# emote-esp8266.net
KiCad netlist of a schematic drawn in EAGLE
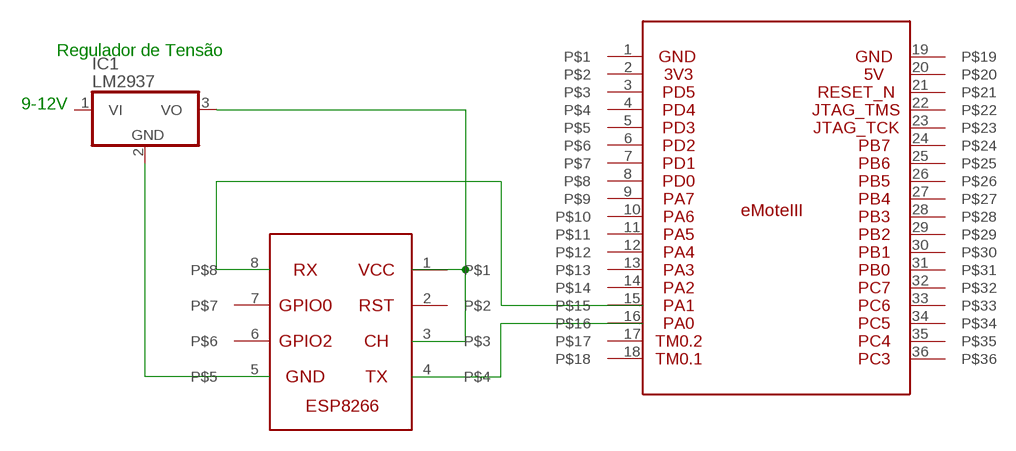
[diagram p0: schematic, sheet 1]

(export (version "E")
  (design (tool "Eeschema 10.0.6"))
  (components
    (comp (ref "IC1")
      (value "LM2937")
      (footprint "eagle-import:TO263-3")
      (libsource (lib "eagle-import") (part "LM2937"))
    )
    (comp (ref "U$1")
      (value "EMOTE3")
      (footprint "eagle-import:2X18")
      (libsource (lib "eagle-import") (part "EMOTE3"))
    )
    (comp (ref "U$2")
      (value "ESP8266")
      (footprint "eagle-import:332-08")
      (libsource (lib "eagle-import") (part "ESP8266"))
    )
  )
  (nets
    (net (code "1") (name "Net-(IC1-GND)") (class "Default")
      (node (ref "IC1") (pin "2") (pinfunction "GND_2") (pintype "passive"))
      (node (ref "U$2") (pin "5") (pinfunction "P$5_5") (pintype "bidirectional"))
    )
    (net (code "2") (name "Net-(IC1-VO)") (class "Default")
      (node (ref "IC1") (pin "3") (pinfunction "VO_3") (pintype "passive"))
      (node (ref "U$2") (pin "1") (pinfunction "P$1_1") (pintype "bidirectional"))
      (node (ref "U$2") (pin "3") (pinfunction "P$3_3") (pintype "bidirectional"))
    )
    (net (code "3") (name "Net-(U$1-P$15)") (class "Default")
      (node (ref "U$1") (pin "15") (pinfunction "P$15_15") (pintype "bidirectional"))
      (node (ref "U$2") (pin "8") (pinfunction "P$8_8") (pintype "bidirectional"))
    )
    (net (code "4") (name "Net-(U$1-P$16)") (class "Default")
      (node (ref "U$1") (pin "16") (pinfunction "P$16_16") (pintype "bidirectional"))
      (node (ref "U$2") (pin "4") (pinfunction "P$4_4") (pintype "bidirectional"))
    )
    (net (code "5") (name "unconnected-(IC1-VI-Pad1)") (class "Default")
      (node (ref "IC1") (pin "1") (pinfunction "VI_1") (pintype "input"))
    )
    (net (code "6") (name "unconnected-(U$1-P$1-Pad1)") (class "Default")
      (node (ref "U$1") (pin "1") (pinfunction "P$1_1") (pintype "bidirectional"))
    )
    (net (code "7") (name "unconnected-(U$1-P$2-Pad2)") (class "Default")
      (node (ref "U$1") (pin "2") (pinfunction "P$2_2") (pintype "bidirectional"))
    )
    (net (code "8") (name "unconnected-(U$1-P$3-Pad3)") (class "Default")
      (node (ref "U$1") (pin "3") (pinfunction "P$3_3") (pintype "bidirectional"))
    )
    (net (code "9") (name "unconnected-(U$1-P$4-Pad4)") (class "Default")
      (node (ref "U$1") (pin "4") (pinfunction "P$4_4") (pintype "bidirectional"))
    )
    (net (code "10") (name "unconnected-(U$1-P$5-Pad5)") (class "Default")
      (node (ref "U$1") (pin "5") (pinfunction "P$5_5") (pintype "bidirectional"))
    )
    (net (code "11") (name "unconnected-(U$1-P$6-Pad6)") (class "Default")
      (node (ref "U$1") (pin "6") (pinfunction "P$6_6") (pintype "bidirectional"))
    )
    (net (code "12") (name "unconnected-(U$1-P$7-Pad7)") (class "Default")
      (node (ref "U$1") (pin "7") (pinfunction "P$7_7") (pintype "bidirectional"))
    )
    (net (code "13") (name "unconnected-(U$1-P$8-Pad8)") (class "Default")
      (node (ref "U$1") (pin "8") (pinfunction "P$8_8") (pintype "bidirectional"))
    )
    (net (code "14") (name "unconnected-(U$1-P$9-Pad9)") (class "Default")
      (node (ref "U$1") (pin "9") (pinfunction "P$9_9") (pintype "bidirectional"))
    )
    (net (code "15") (name "unconnected-(U$1-P$10-Pad10)") (class "Default")
      (node (ref "U$1") (pin "10") (pinfunction "P$10_10") (pintype "bidirectional"))
    )
    (net (code "16") (name "unconnected-(U$1-P$11-Pad11)") (class "Default")
      (node (ref "U$1") (pin "11") (pinfunction "P$11_11") (pintype "bidirectional"))
    )
    (net (code "17") (name "unconnected-(U$1-P$12-Pad12)") (class "Default")
      (node (ref "U$1") (pin "12") (pinfunction "P$12_12") (pintype "bidirectional"))
    )
    (net (code "18") (name "unconnected-(U$1-P$13-Pad13)") (class "Default")
      (node (ref "U$1") (pin "13") (pinfunction "P$13_13") (pintype "bidirectional"))
    )
    (net (code "19") (name "unconnected-(U$1-P$14-Pad14)") (class "Default")
      (node (ref "U$1") (pin "14") (pinfunction "P$14_14") (pintype "bidirectional"))
    )
    (net (code "20") (name "unconnected-(U$1-P$17-Pad17)") (class "Default")
      (node (ref "U$1") (pin "17") (pinfunction "P$17_17") (pintype "bidirectional"))
    )
    (net (code "21") (name "unconnected-(U$1-P$18-Pad18)") (class "Default")
      (node (ref "U$1") (pin "18") (pinfunction "P$18_18") (pintype "bidirectional"))
    )
    (net (code "22") (name "unconnected-(U$1-P$19-Pad19)") (class "Default")
      (node (ref "U$1") (pin "19") (pinfunction "P$19_19") (pintype "bidirectional"))
    )
    (net (code "23") (name "unconnected-(U$1-P$20-Pad20)") (class "Default")
      (node (ref "U$1") (pin "20") (pinfunction "P$20_20") (pintype "bidirectional"))
    )
    (net (code "24") (name "unconnected-(U$1-P$21-Pad21)") (class "Default")
      (node (ref "U$1") (pin "21") (pinfunction "P$21_21") (pintype "bidirectional"))
    )
    (net (code "25") (name "unconnected-(U$1-P$22-Pad22)") (class "Default")
      (node (ref "U$1") (pin "22") (pinfunction "P$22_22") (pintype "bidirectional"))
    )
    (net (code "26") (name "unconnected-(U$1-P$23-Pad23)") (class "Default")
      (node (ref "U$1") (pin "23") (pinfunction "P$23_23") (pintype "bidirectional"))
    )
    (net (code "27") (name "unconnected-(U$1-P$24-Pad24)") (class "Default")
      (node (ref "U$1") (pin "24") (pinfunction "P$24_24") (pintype "bidirectional"))
    )
    (net (code "28") (name "unconnected-(U$1-P$25-Pad25)") (class "Default")
      (node (ref "U$1") (pin "25") (pinfunction "P$25_25") (pintype "bidirectional"))
    )
    (net (code "29") (name "unconnected-(U$1-P$26-Pad26)") (class "Default")
      (node (ref "U$1") (pin "26") (pinfunction "P$26_26") (pintype "bidirectional"))
    )
    (net (code "30") (name "unconnected-(U$1-P$27-Pad27)") (class "Default")
      (node (ref "U$1") (pin "27") (pinfunction "P$27_27") (pintype "bidirectional"))
    )
    (net (code "31") (name "unconnected-(U$1-P$28-Pad28)") (class "Default")
      (node (ref "U$1") (pin "28") (pinfunction "P$28_28") (pintype "bidirectional"))
    )
    (net (code "32") (name "unconnected-(U$1-P$29-Pad29)") (class "Default")
      (node (ref "U$1") (pin "29") (pinfunction "P$29_29") (pintype "bidirectional"))
    )
    (net (code "33") (name "unconnected-(U$1-P$30-Pad30)") (class "Default")
      (node (ref "U$1") (pin "30") (pinfunction "P$30_30") (pintype "bidirectional"))
    )
    (net (code "34") (name "unconnected-(U$1-P$31-Pad31)") (class "Default")
      (node (ref "U$1") (pin "31") (pinfunction "P$31_31") (pintype "bidirectional"))
    )
    (net (code "35") (name "unconnected-(U$1-P$32-Pad32)") (class "Default")
      (node (ref "U$1") (pin "32") (pinfunction "P$32_32") (pintype "bidirectional"))
    )
    (net (code "36") (name "unconnected-(U$1-P$33-Pad33)") (class "Default")
      (node (ref "U$1") (pin "33") (pinfunction "P$33_33") (pintype "bidirectional"))
    )
    (net (code "37") (name "unconnected-(U$1-P$34-Pad34)") (class "Default")
      (node (ref "U$1") (pin "34") (pinfunction "P$34_34") (pintype "bidirectional"))
    )
    (net (code "38") (name "unconnected-(U$1-P$35-Pad35)") (class "Default")
      (node (ref "U$1") (pin "35") (pinfunction "P$35_35") (pintype "bidirectional"))
    )
    (net (code "39") (name "unconnected-(U$1-P$36-Pad36)") (class "Default")
      (node (ref "U$1") (pin "36") (pinfunction "P$36_36") (pintype "bidirectional"))
    )
    (net (code "40") (name "unconnected-(U$2-P$2-Pad2)") (class "Default")
      (node (ref "U$2") (pin "2") (pinfunction "P$2_2") (pintype "bidirectional"))
    )
    (net (code "41") (name "unconnected-(U$2-P$6-Pad6)") (class "Default")
      (node (ref "U$2") (pin "6") (pinfunction "P$6_6") (pintype "bidirectional"))
    )
    (net (code "42") (name "unconnected-(U$2-P$7-Pad7)") (class "Default")
      (node (ref "U$2") (pin "7") (pinfunction "P$7_7") (pintype "bidirectional"))
    )
  )
)
